# oshi-fuse-board-mk-2_5x20mm.net
KiCad netlist of a schematic drawn in EAGLE
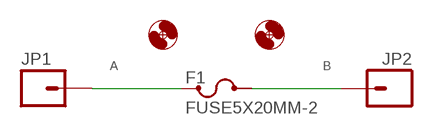
[diagram p0: schematic, sheet 1]

(export (version "E")
  (design (tool "Eeschema 10.0.6"))
  (components
    (comp (ref "F1")
      (value "FUSE5X20MM-2")
      (footprint "eagle-import:FUSE-2AG")
      (libsource (lib "eagle-import") (part "FUSE5X20MM-2"))
    )
    (comp (ref "H1")
      (value "HOLE#2")
      (footprint "eagle-import:HOLE-#2")
      (libsource (lib "eagle-import") (part "HOLE#2"))
    )
    (comp (ref "H2")
      (value "HOLE#2")
      (footprint "eagle-import:HOLE-#2")
      (libsource (lib "eagle-import") (part "HOLE#2"))
    )
    (comp (ref "JP1")
      (value "M01SCREWITGOOD")
      (footprint "eagle-import:1X01-RING-TERM-6-32-FAT")
      (libsource (lib "eagle-import") (part "M01SCREWITGOOD"))
    )
    (comp (ref "JP2")
      (value "M01SCREWITGOOD")
      (footprint "eagle-import:1X01-RING-TERM-6-32-FAT")
      (libsource (lib "eagle-import") (part "M01SCREWITGOOD"))
    )
  )
  (nets
    (net (code "1") (name "/A") (class "Default")
      (node (ref "F1") (pin "1") (pinfunction "1_1") (pintype "passive"))
      (node (ref "F1") (pin "1@1") (pinfunction "1_1@1") (pintype "passive"))
      (node (ref "JP1") (pin "P$1") (pinfunction "1_P$1") (pintype "passive"))
      (node (ref "JP1") (pin "P$2") (pinfunction "1_P$2") (pintype "passive"))
      (node (ref "JP1") (pin "P$3") (pinfunction "1_P$3") (pintype "passive"))
      (node (ref "JP1") (pin "P$4") (pinfunction "1_P$4") (pintype "passive"))
    )
    (net (code "2") (name "/B") (class "Default")
      (node (ref "F1") (pin "2") (pinfunction "2_2") (pintype "passive"))
      (node (ref "F1") (pin "2@2") (pinfunction "2_2@2") (pintype "passive"))
      (node (ref "JP2") (pin "P$1") (pinfunction "1_P$1") (pintype "passive"))
      (node (ref "JP2") (pin "P$2") (pinfunction "1_P$2") (pintype "passive"))
      (node (ref "JP2") (pin "P$3") (pinfunction "1_P$3") (pintype "passive"))
      (node (ref "JP2") (pin "P$4") (pinfunction "1_P$4") (pintype "passive"))
    )
  )
)
